# Audrino_7Seg_2020-07-23_17-01-29.net
KiCad netlist of a schematic drawn in EasyEDA
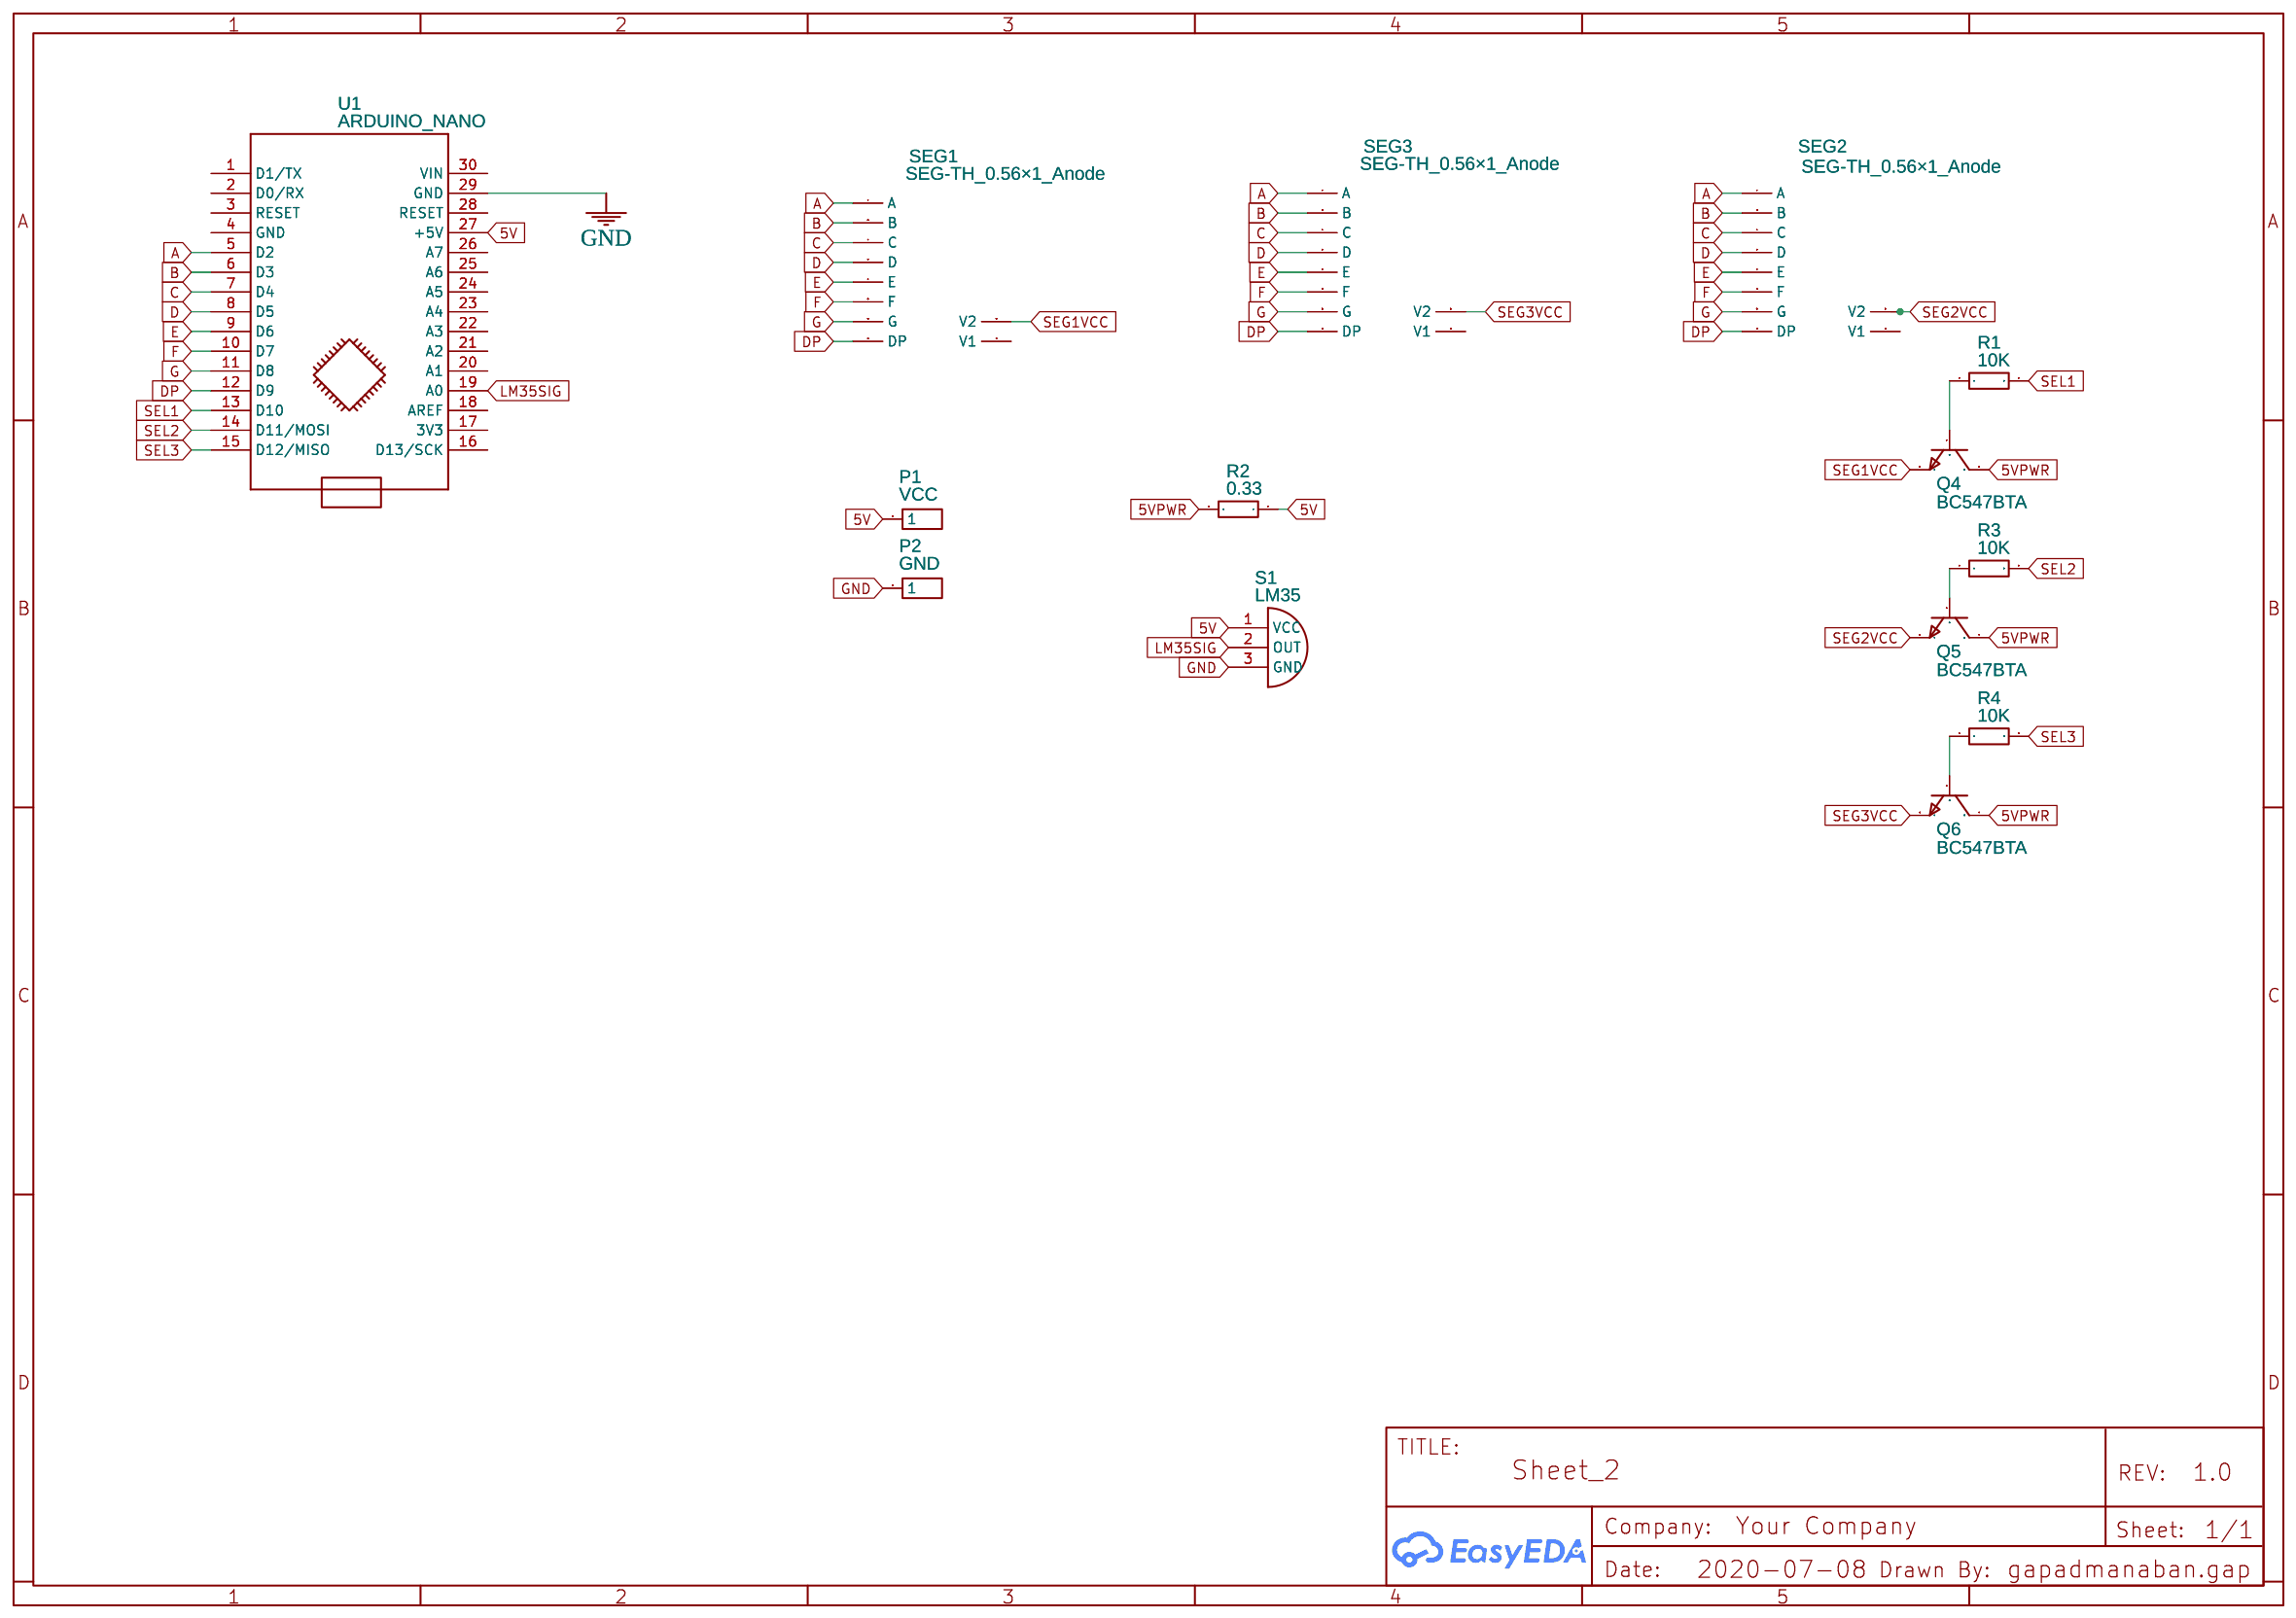
[diagram p0: schematic sheet]

(export (version "E")
  (design (tool "Eeschema 10.0.6"))
  (components
    (comp (ref "P1")
      (value "VCC")
      (fields
        (field (name "BOM_Manufacturer Part") "Header-Male-2.54_1x1")
        (field (name "BOM_Supplier Part") "C81276")
      )
      (libsource (lib "") (part "Header-Male-2.54_1x1"))
    )
    (comp (ref "P2")
      (value "GND")
      (fields
        (field (name "BOM_Manufacturer Part") "Header-Male-2.54_1x1")
        (field (name "BOM_Supplier Part") "C81276")
      )
      (libsource (lib "") (part "Header-Male-2.54_1x1"))
    )
    (comp (ref "Q4")
      (value "BC547BTA")
      (fields (field (name "BOM_Supplier Part") "C258144"))
      (libsource (lib "") (part "BC547BTA"))
    )
    (comp (ref "Q5")
      (value "BC547BTA")
      (fields (field (name "BOM_Supplier Part") "C258144"))
      (libsource (lib "") (part "BC547BTA"))
    )
    (comp (ref "Q6")
      (value "BC547BTA")
      (fields (field (name "BOM_Supplier Part") "C258144"))
      (libsource (lib "") (part "BC547BTA"))
    )
    (comp (ref "R1")
      (value "10K")
      (fields
        (field (name "BOM_Manufacturer Part") "MO2WS-0R33±5%-6T63")
        (field (name "BOM_Supplier Part") "C479460")
      )
      (libsource (lib "") (part "MO2WS-0R33±5%-6T63"))
    )
    (comp (ref "R2")
      (value "0.33")
      (fields
        (field (name "BOM_Manufacturer Part") "MO2WS-0R33±5%-6T63")
        (field (name "BOM_Supplier Part") "C479460")
      )
      (libsource (lib "") (part "MO2WS-0R33±5%-6T63_1"))
    )
    (comp (ref "R3")
      (value "10K")
      (fields
        (field (name "BOM_Manufacturer Part") "MO2WS-0R33±5%-6T63")
        (field (name "BOM_Supplier Part") "C479460")
      )
      (libsource (lib "") (part "MO2WS-0R33±5%-6T63"))
    )
    (comp (ref "R4")
      (value "10K")
      (fields
        (field (name "BOM_Manufacturer Part") "MO2WS-0R33±5%-6T63")
        (field (name "BOM_Supplier Part") "C479460")
      )
      (libsource (lib "") (part "MO2WS-0R33±5%-6T63"))
    )
    (comp (ref "S1")
      (value "LM35")
      (fields (field (name "BOM_Manufacturer Part") "?"))
      (libsource (lib "") (part "Unknown_635_-485"))
    )
    (comp (ref "SEG1")
      (value "SEG-TH_0.56×1_Anode")
      (fields (field (name "BOM_Supplier Part") "C8092"))
      (libsource (lib "") (part "SEG-TH_0.56×1_Anode"))
    )
    (comp (ref "SEG2")
      (value "SEG-TH_0.56×1_Anode")
      (fields (field (name "BOM_Supplier Part") "C8092"))
      (libsource (lib "") (part "SEG-TH_0.56×1_Anode"))
    )
    (comp (ref "SEG3")
      (value "SEG-TH_0.56×1_Anode")
      (fields (field (name "BOM_Supplier Part") "C8092"))
      (libsource (lib "") (part "SEG-TH_0.56×1_Anode"))
    )
    (comp (ref "U1") (value "ARDUINO_NANO") (libsource (lib "") (part "ARDUINO_NANO")))
  )
  (nets
    (net (code "1") (name "5V") (class "Default")
      (node (ref "P1") (pin "1") (pinfunction "1_1") (pintype "input"))
      (node (ref "R2") (pin "1") (pinfunction "1_1") (pintype "unspecified"))
      (node (ref "S1") (pin "1") (pinfunction "VCC_1") (pintype "unspecified"))
      (node (ref "U1") (pin "27") (pinfunction "+5V_27") (pintype "unspecified"))
    )
    (net (code "2") (name "5VPWR") (class "Default")
      (node (ref "Q4") (pin "1") (pinfunction "C_1") (pintype "unspecified"))
      (node (ref "Q5") (pin "1") (pinfunction "C_1") (pintype "unspecified"))
      (node (ref "Q6") (pin "1") (pinfunction "C_1") (pintype "unspecified"))
      (node (ref "R2") (pin "2") (pinfunction "2_2") (pintype "unspecified"))
    )
    (net (code "3") (name "A") (class "Default")
      (node (ref "SEG1") (pin "7") (pinfunction "A_7") (pintype "unspecified"))
      (node (ref "SEG2") (pin "7") (pinfunction "A_7") (pintype "unspecified"))
      (node (ref "SEG3") (pin "7") (pinfunction "A_7") (pintype "unspecified"))
      (node (ref "U1") (pin "5") (pinfunction "D2_5") (pintype "unspecified"))
    )
    (net (code "4") (name "B") (class "Default")
      (node (ref "SEG1") (pin "6") (pinfunction "B_6") (pintype "unspecified"))
      (node (ref "SEG2") (pin "6") (pinfunction "B_6") (pintype "unspecified"))
      (node (ref "SEG3") (pin "6") (pinfunction "B_6") (pintype "unspecified"))
      (node (ref "U1") (pin "6") (pinfunction "D3_6") (pintype "unspecified"))
    )
    (net (code "5") (name "C") (class "Default")
      (node (ref "SEG1") (pin "4") (pinfunction "C_4") (pintype "unspecified"))
      (node (ref "SEG2") (pin "4") (pinfunction "C_4") (pintype "unspecified"))
      (node (ref "SEG3") (pin "4") (pinfunction "C_4") (pintype "unspecified"))
      (node (ref "U1") (pin "7") (pinfunction "D4_7") (pintype "unspecified"))
    )
    (net (code "6") (name "D") (class "Default")
      (node (ref "SEG1") (pin "2") (pinfunction "D_2") (pintype "unspecified"))
      (node (ref "SEG2") (pin "2") (pinfunction "D_2") (pintype "unspecified"))
      (node (ref "SEG3") (pin "2") (pinfunction "D_2") (pintype "unspecified"))
      (node (ref "U1") (pin "8") (pinfunction "D5_8") (pintype "unspecified"))
    )
    (net (code "7") (name "DP") (class "Default")
      (node (ref "SEG1") (pin "5") (pinfunction "DP_5") (pintype "unspecified"))
      (node (ref "SEG2") (pin "5") (pinfunction "DP_5") (pintype "unspecified"))
      (node (ref "SEG3") (pin "5") (pinfunction "DP_5") (pintype "unspecified"))
      (node (ref "U1") (pin "12") (pinfunction "D9_12") (pintype "unspecified"))
    )
    (net (code "8") (name "E") (class "Default")
      (node (ref "SEG1") (pin "1") (pinfunction "E_1") (pintype "unspecified"))
      (node (ref "SEG2") (pin "1") (pinfunction "E_1") (pintype "unspecified"))
      (node (ref "SEG3") (pin "1") (pinfunction "E_1") (pintype "unspecified"))
      (node (ref "U1") (pin "9") (pinfunction "D6_9") (pintype "unspecified"))
    )
    (net (code "9") (name "F") (class "Default")
      (node (ref "SEG1") (pin "9") (pinfunction "F_9") (pintype "unspecified"))
      (node (ref "SEG2") (pin "9") (pinfunction "F_9") (pintype "unspecified"))
      (node (ref "SEG3") (pin "9") (pinfunction "F_9") (pintype "unspecified"))
      (node (ref "U1") (pin "10") (pinfunction "D7_10") (pintype "unspecified"))
    )
    (net (code "10") (name "G") (class "Default")
      (node (ref "SEG1") (pin "10") (pinfunction "G_10") (pintype "unspecified"))
      (node (ref "SEG2") (pin "10") (pinfunction "G_10") (pintype "unspecified"))
      (node (ref "SEG3") (pin "10") (pinfunction "G_10") (pintype "unspecified"))
      (node (ref "U1") (pin "11") (pinfunction "D8_11") (pintype "unspecified"))
    )
    (net (code "11") (name "GND") (class "Default")
      (node (ref "P2") (pin "1") (pinfunction "1_1") (pintype "input"))
      (node (ref "S1") (pin "3") (pinfunction "GND_3") (pintype "unspecified"))
      (node (ref "U1") (pin "29") (pinfunction "GND_29") (pintype "unspecified"))
    )
    (net (code "12") (name "LM35SIG") (class "Default")
      (node (ref "S1") (pin "2") (pinfunction "OUT_2") (pintype "unspecified"))
      (node (ref "U1") (pin "19") (pinfunction "A0_19") (pintype "unspecified"))
    )
    (net (code "13") (name "Net-(Q4-B)") (class "Default")
      (node (ref "Q4") (pin "2") (pinfunction "B_2") (pintype "unspecified"))
      (node (ref "R1") (pin "1") (pinfunction "1_1") (pintype "unspecified"))
    )
    (net (code "14") (name "Net-(Q5-B)") (class "Default")
      (node (ref "Q5") (pin "2") (pinfunction "B_2") (pintype "unspecified"))
      (node (ref "R3") (pin "1") (pinfunction "1_1") (pintype "unspecified"))
    )
    (net (code "15") (name "Net-(Q6-B)") (class "Default")
      (node (ref "Q6") (pin "2") (pinfunction "B_2") (pintype "unspecified"))
      (node (ref "R4") (pin "1") (pinfunction "1_1") (pintype "unspecified"))
    )
    (net (code "16") (name "SEG1VCC") (class "Default")
      (node (ref "Q4") (pin "3") (pinfunction "E_3") (pintype "unspecified"))
      (node (ref "SEG1") (pin "8") (pinfunction "V2_8") (pintype "unspecified"))
    )
    (net (code "17") (name "SEG2VCC") (class "Default")
      (node (ref "Q5") (pin "3") (pinfunction "E_3") (pintype "unspecified"))
      (node (ref "SEG2") (pin "8") (pinfunction "V2_8") (pintype "unspecified"))
    )
    (net (code "18") (name "SEG3VCC") (class "Default")
      (node (ref "Q6") (pin "3") (pinfunction "E_3") (pintype "unspecified"))
      (node (ref "SEG3") (pin "8") (pinfunction "V2_8") (pintype "unspecified"))
    )
    (net (code "19") (name "SEL1") (class "Default")
      (node (ref "R1") (pin "2") (pinfunction "2_2") (pintype "unspecified"))
      (node (ref "U1") (pin "13") (pinfunction "D10_13") (pintype "unspecified"))
    )
    (net (code "20") (name "SEL2") (class "Default")
      (node (ref "R3") (pin "2") (pinfunction "2_2") (pintype "unspecified"))
      (node (ref "U1") (pin "14") (pinfunction "D11/MOSI_14") (pintype "unspecified"))
    )
    (net (code "21") (name "SEL3") (class "Default")
      (node (ref "R4") (pin "2") (pinfunction "2_2") (pintype "unspecified"))
      (node (ref "U1") (pin "15") (pinfunction "D12/MISO_15") (pintype "unspecified"))
    )
    (net (code "22") (name "unconnected-(SEG1-V1-Pad3)") (class "Default")
      (node (ref "SEG1") (pin "3") (pinfunction "V1_3") (pintype "unspecified"))
    )
    (net (code "23") (name "unconnected-(SEG2-V1-Pad3)") (class "Default")
      (node (ref "SEG2") (pin "3") (pinfunction "V1_3") (pintype "unspecified"))
    )
    (net (code "24") (name "unconnected-(SEG3-V1-Pad3)") (class "Default")
      (node (ref "SEG3") (pin "3") (pinfunction "V1_3") (pintype "unspecified"))
    )
    (net (code "25") (name "unconnected-(U1-3V3-Pad17)") (class "Default")
      (node (ref "U1") (pin "17") (pinfunction "3V3_17") (pintype "unspecified"))
    )
    (net (code "26") (name "unconnected-(U1-A1-Pad20)") (class "Default")
      (node (ref "U1") (pin "20") (pinfunction "A1_20") (pintype "unspecified"))
    )
    (net (code "27") (name "unconnected-(U1-A2-Pad21)") (class "Default")
      (node (ref "U1") (pin "21") (pinfunction "A2_21") (pintype "unspecified"))
    )
    (net (code "28") (name "unconnected-(U1-A3-Pad22)") (class "Default")
      (node (ref "U1") (pin "22") (pinfunction "A3_22") (pintype "unspecified"))
    )
    (net (code "29") (name "unconnected-(U1-A4-Pad23)") (class "Default")
      (node (ref "U1") (pin "23") (pinfunction "A4_23") (pintype "unspecified"))
    )
    (net (code "30") (name "unconnected-(U1-A5-Pad24)") (class "Default")
      (node (ref "U1") (pin "24") (pinfunction "A5_24") (pintype "unspecified"))
    )
    (net (code "31") (name "unconnected-(U1-A6-Pad25)") (class "Default")
      (node (ref "U1") (pin "25") (pinfunction "A6_25") (pintype "unspecified"))
    )
    (net (code "32") (name "unconnected-(U1-A7-Pad26)") (class "Default")
      (node (ref "U1") (pin "26") (pinfunction "A7_26") (pintype "unspecified"))
    )
    (net (code "33") (name "unconnected-(U1-AREF-Pad18)") (class "Default")
      (node (ref "U1") (pin "18") (pinfunction "AREF_18") (pintype "unspecified"))
    )
    (net (code "34") (name "unconnected-(U1-D0{slash}RX-Pad2)") (class "Default")
      (node (ref "U1") (pin "2") (pinfunction "D0/RX_2") (pintype "unspecified"))
    )
    (net (code "35") (name "unconnected-(U1-D1{slash}TX-Pad1)") (class "Default")
      (node (ref "U1") (pin "1") (pinfunction "D1/TX_1") (pintype "unspecified"))
    )
    (net (code "36") (name "unconnected-(U1-D13{slash}SCK-Pad16)") (class "Default")
      (node (ref "U1") (pin "16") (pinfunction "D13/SCK_16") (pintype "unspecified"))
    )
    (net (code "37") (name "unconnected-(U1-GND-Pad4)") (class "Default")
      (node (ref "U1") (pin "4") (pinfunction "GND_4") (pintype "unspecified"))
    )
    (net (code "38") (name "unconnected-(U1-RESET-Pad3)") (class "Default")
      (node (ref "U1") (pin "3") (pinfunction "RESET_3") (pintype "unspecified"))
    )
    (net (code "39") (name "unconnected-(U1-RESET-Pad28)") (class "Default")
      (node (ref "U1") (pin "28") (pinfunction "RESET_28") (pintype "unspecified"))
    )
    (net (code "40") (name "unconnected-(U1-VIN-Pad30)") (class "Default")
      (node (ref "U1") (pin "30") (pinfunction "VIN_30") (pintype "unspecified"))
    )
  )
)
